# ZED-F9T.net
KiCad netlist of a schematic drawn in Altium Designer
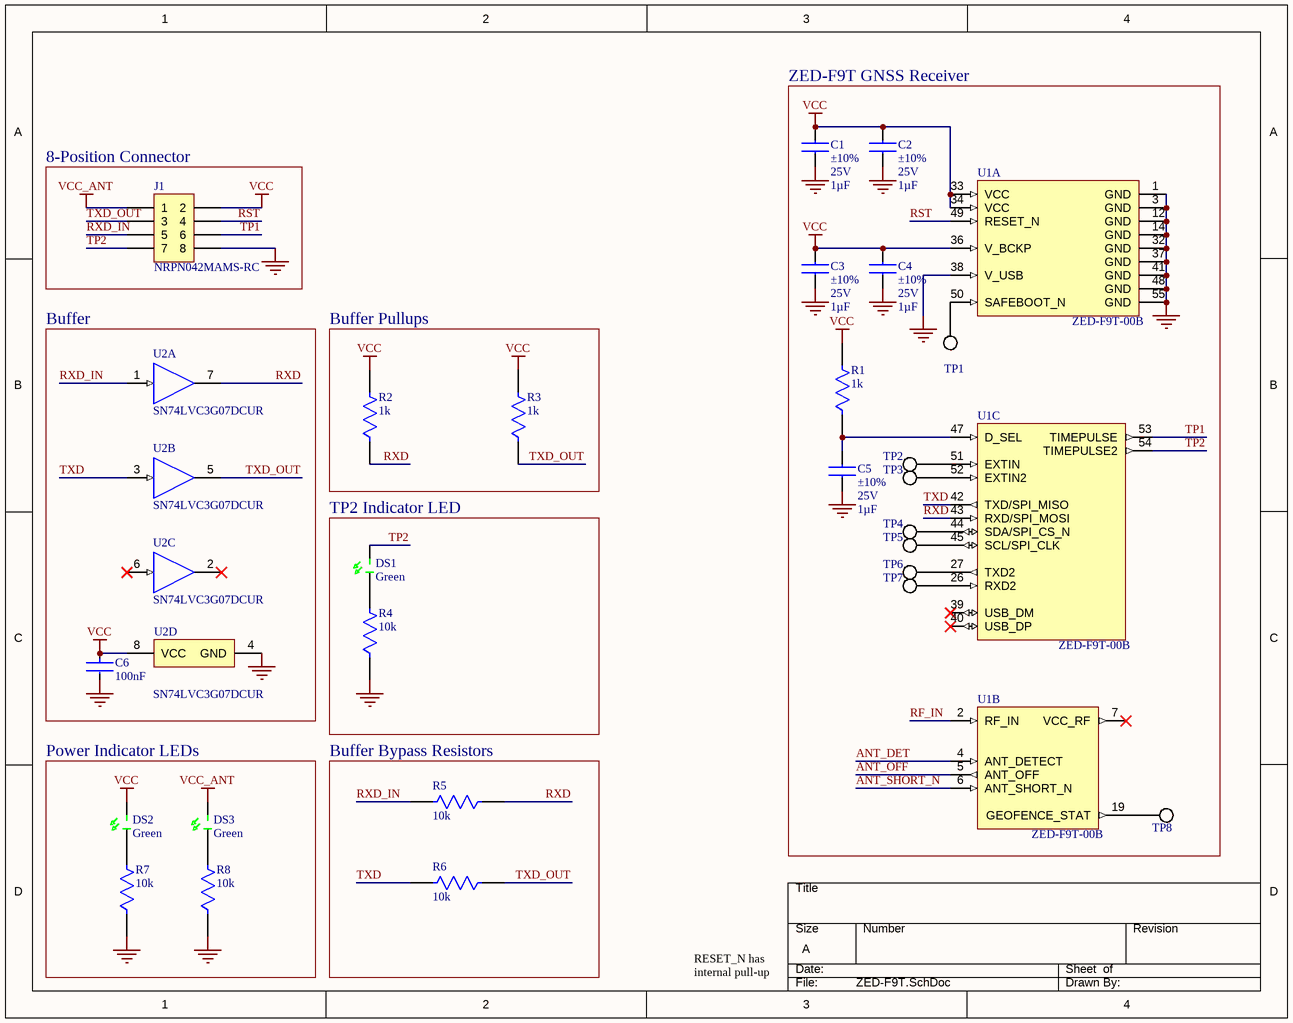
[diagram p0: ZED-F9T.SchDoc]

(export (version "E")
  (design (tool "Eeschema 10.0.6"))
  (components
    (comp (ref "C1")
      (value "Murata_GRM155R61E105KA12D")
      (footprint "CAPC1005X055N")
      (description "CAP, CER, X5R, 1UF, 10%, 25V, 0402, 0.55MM T")
      (fields
        (field (name "MANUFACTURER PART NUMBER") "GRM155R61E105KA12D")
        (field (name "TOLERANCE") "±10%")
        (field (name "VOLTAGE RATING") "25V")
        (field (name "MANUFACTURER") "Murata")
        (field (name "CAPACITANCE") "1µF")
      )
      (libsource (lib "RL Research Altium Server") (part "Capacitor_300mil"))
    )
    (comp (ref "C2")
      (value "Murata_GRM155R61E105KA12D")
      (footprint "CAPC1005X055N")
      (description "CAP, CER, X5R, 1UF, 10%, 25V, 0402, 0.55MM T")
      (fields
        (field (name "MANUFACTURER PART NUMBER") "GRM155R61E105KA12D")
        (field (name "TOLERANCE") "±10%")
        (field (name "VOLTAGE RATING") "25V")
        (field (name "MANUFACTURER") "Murata")
        (field (name "CAPACITANCE") "1µF")
      )
      (libsource (lib "RL Research Altium Server") (part "Capacitor_300mil"))
    )
    (comp (ref "C3")
      (value "Murata_GRM155R61E105KA12D")
      (footprint "CAPC1005X055N")
      (description "CAP, CER, X5R, 1UF, 10%, 25V, 0402, 0.55MM T")
      (fields
        (field (name "MANUFACTURER PART NUMBER") "GRM155R61E105KA12D")
        (field (name "TOLERANCE") "±10%")
        (field (name "VOLTAGE RATING") "25V")
        (field (name "MANUFACTURER") "Murata")
        (field (name "CAPACITANCE") "1µF")
      )
      (libsource (lib "RL Research Altium Server") (part "Capacitor_300mil"))
    )
    (comp (ref "C4")
      (value "Murata_GRM155R61E105KA12D")
      (footprint "CAPC1005X055N")
      (description "CAP, CER, X5R, 1UF, 10%, 25V, 0402, 0.55MM T")
      (fields
        (field (name "MANUFACTURER PART NUMBER") "GRM155R61E105KA12D")
        (field (name "TOLERANCE") "±10%")
        (field (name "VOLTAGE RATING") "25V")
        (field (name "MANUFACTURER") "Murata")
        (field (name "CAPACITANCE") "1µF")
      )
      (libsource (lib "RL Research Altium Server") (part "Capacitor_300mil"))
    )
    (comp (ref "C5")
      (value "Murata_GRM155R61E105KA12D")
      (footprint "CAPC1005X055N")
      (description "CAP, CER, X5R, 1UF, 10%, 25V, 0402, 0.55MM T")
      (fields
        (field (name "MANUFACTURER PART NUMBER") "GRM155R61E105KA12D")
        (field (name "TOLERANCE") "±10%")
        (field (name "VOLTAGE RATING") "25V")
        (field (name "MANUFACTURER") "Murata")
        (field (name "CAPACITANCE") "1µF")
      )
      (libsource (lib "RL Research Altium Server") (part "Capacitor_300mil"))
    )
    (comp (ref "C6")
      (value "100nF")
      (footprint "FP-0402-L_1_0_0_05-W_0_5-IPC_B")
      (description "None")
      (fields (field (name "TOLERANCE") "10%"))
      (libsource (lib "Altium Content Vault") (part "b4654b650e69147ec39a6b967a45e02"))
    )
    (comp (ref "DS1")
      (value "Lumex_SML-LXFM0603SUGCTR")
      (footprint "LEDS160X80X110-2N_LXFM0603-GR")
      (description "LED, GREEN, 574NM, 20MA, 20MCD MIN, 2.5VF MAX, 0603, 1.10MM T")
      (fields
        (field (name "INTERNAL PART NUMBER") "838-00422-00")
        (field (name "MANUFACTURER") "Lumex Opto/Components Inc.")
        (field (name "COLOR") "Green")
      )
      (libsource (lib "RL Research Altium Server") (part "LED_Green_300mil"))
    )
    (comp (ref "DS2")
      (value "Lumex_SML-LXFM0603SUGCTR")
      (footprint "LEDS160X80X110-2N_LXFM0603-GR")
      (description "LED, GREEN, 574NM, 20MA, 20MCD MIN, 2.5VF MAX, 0603, 1.10MM T")
      (fields
        (field (name "INTERNAL PART NUMBER") "838-00422-00")
        (field (name "MANUFACTURER") "Lumex Opto/Components Inc.")
        (field (name "COLOR") "Green")
      )
      (libsource (lib "RL Research Altium Server") (part "LED_Green_300mil"))
    )
    (comp (ref "DS3")
      (value "Lumex_SML-LXFM0603SUGCTR")
      (footprint "LEDS160X80X110-2N_LXFM0603-GR")
      (description "LED, GREEN, 574NM, 20MA, 20MCD MIN, 2.5VF MAX, 0603, 1.10MM T")
      (fields
        (field (name "INTERNAL PART NUMBER") "838-00422-00")
        (field (name "MANUFACTURER") "Lumex Opto/Components Inc.")
        (field (name "COLOR") "Green")
      )
      (libsource (lib "RL Research Altium Server") (part "LED_Green_300mil"))
    )
    (comp (ref "J1")
      (value "NRPN042MAMS-RC")
      (footprint "NRPN042MAMS-RC")
      (description "Dual Row 8 Position 2 mm Pitch Surface Mount Header")
      (fields (field (name "MANUFACTURER") "Sullins"))
      (libsource (lib "GNSS_Receiver_Library") (part "NRPN042MAMS-RC"))
    )
    (comp (ref "R1")
      (value "1k")
      (footprint "FP-RMCF0402-MFG")
      (description "1kΩ ±1% 0.063W 0402 Thick Film Chip Resistor AEC-Q200 compliant")
      (fields (field (name "TOLERANCE") "1%"))
      (libsource (lib "Altium Content Vault") (part "1029c3af85768c4190bb7ad29bc67b5"))
    )
    (comp (ref "R2")
      (value "1k")
      (footprint "FP-RMCF0402-MFG")
      (description "1kΩ ±1% 0.063W 0402 Thick Film Chip Resistor AEC-Q200 compliant")
      (fields (field (name "TOLERANCE") "1%"))
      (libsource (lib "Altium Content Vault") (part "1029c3af85768c4190bb7ad29bc67b5"))
    )
    (comp (ref "R3")
      (value "1k")
      (footprint "FP-RMCF0402-MFG")
      (description "1kΩ ±1% 0.063W 0402 Thick Film Chip Resistor AEC-Q200 compliant")
      (fields (field (name "TOLERANCE") "1%"))
      (libsource (lib "Altium Content Vault") (part "1029c3af85768c4190bb7ad29bc67b5"))
    )
    (comp (ref "R4")
      (value "10k")
      (footprint "FP-RMCF0402-IPC_C")
      (description "10kΩ ±1% 0.063W 0402 Thick Film Chip Resistor AEC-Q200 compliant")
      (fields (field (name "TOLERANCE") "1%"))
      (libsource (lib "Altium Content Vault") (part "1029c3af85768c4190bb7ad29bc67b5"))
    )
    (comp (ref "R5")
      (value "10k")
      (footprint "FP-RMCF0402-IPC_C")
      (description "10kΩ ±1% 0.063W 0402 Thick Film Chip Resistor AEC-Q200 compliant")
      (fields (field (name "TOLERANCE") "1%"))
      (libsource (lib "Altium Content Vault") (part "1029c3af85768c4190bb7ad29bc67b5"))
    )
    (comp (ref "R6")
      (value "10k")
      (footprint "FP-RMCF0402-IPC_C")
      (description "10kΩ ±1% 0.063W 0402 Thick Film Chip Resistor AEC-Q200 compliant")
      (fields (field (name "TOLERANCE") "1%"))
      (libsource (lib "Altium Content Vault") (part "1029c3af85768c4190bb7ad29bc67b5"))
    )
    (comp (ref "R7")
      (value "10k")
      (footprint "FP-RMCF0402-IPC_C")
      (description "10kΩ ±1% 0.063W 0402 Thick Film Chip Resistor AEC-Q200 compliant")
      (fields (field (name "TOLERANCE") "1%"))
      (libsource (lib "Altium Content Vault") (part "1029c3af85768c4190bb7ad29bc67b5"))
    )
    (comp (ref "R8")
      (value "10k")
      (footprint "FP-RMCF0402-IPC_C")
      (description "10kΩ ±1% 0.063W 0402 Thick Film Chip Resistor AEC-Q200 compliant")
      (fields (field (name "TOLERANCE") "1%"))
      (libsource (lib "Altium Content Vault") (part "1029c3af85768c4190bb7ad29bc67b5"))
    )
    (comp (ref "TP1")
      (value "SMT_100DIA")
      (footprint "TP001V_SMT_100DIA")
      (description "TEST POINT, PC, SMT, 1.00MM DIA")
      (libsource (lib "RL Research Altium Server") (part "TP_NoColor_001pin_No_BOM"))
    )
    (comp (ref "TP2")
      (value "SMT_100DIA")
      (footprint "TP001V_SMT_100DIA")
      (description "TEST POINT, PC, SMT, 1.00MM DIA")
      (libsource (lib "RL Research Altium Server") (part "TP_NoColor_001pin_No_BOM"))
    )
    (comp (ref "TP3")
      (value "SMT_100DIA")
      (footprint "TP001V_SMT_100DIA")
      (description "TEST POINT, PC, SMT, 1.00MM DIA")
      (libsource (lib "RL Research Altium Server") (part "TP_NoColor_001pin_No_BOM"))
    )
    (comp (ref "TP4")
      (value "SMT_100DIA")
      (footprint "TP001V_SMT_100DIA")
      (description "TEST POINT, PC, SMT, 1.00MM DIA")
      (libsource (lib "RL Research Altium Server") (part "TP_NoColor_001pin_No_BOM"))
    )
    (comp (ref "TP5")
      (value "SMT_100DIA")
      (footprint "TP001V_SMT_100DIA")
      (description "TEST POINT, PC, SMT, 1.00MM DIA")
      (libsource (lib "RL Research Altium Server") (part "TP_NoColor_001pin_No_BOM"))
    )
    (comp (ref "TP6")
      (value "SMT_100DIA")
      (footprint "TP001V_SMT_100DIA")
      (description "TEST POINT, PC, SMT, 1.00MM DIA")
      (libsource (lib "RL Research Altium Server") (part "TP_NoColor_001pin_No_BOM"))
    )
    (comp (ref "TP7")
      (value "SMT_100DIA")
      (footprint "TP001V_SMT_100DIA")
      (description "TEST POINT, PC, SMT, 1.00MM DIA")
      (libsource (lib "RL Research Altium Server") (part "TP_NoColor_001pin_No_BOM"))
    )
    (comp (ref "TP8")
      (value "SMT_100DIA")
      (footprint "TP001V_SMT_100DIA")
      (description "TEST POINT, PC, SMT, 1.00MM DIA")
      (libsource (lib "RL Research Altium Server") (part "TP_NoColor_001pin_No_BOM"))
    )
    (comp (ref "U1")
      (value "ZED-F9T-00B")
      (footprint "GPS_ZED-F9T")
      (description "Multi-band GNSS Receiver with Nanosecond-level Timing Accuracy")
      (fields (field (name "MANUFACTURER") "u-blox"))
      (libsource (lib "GNSS_Receiver_Library") (part "GPS_ZED-F9T"))
    )
    (comp (ref "U2")
      (value "SN74LVC3G07DCUR")
      (footprint "DCU0008A_N")
      (description "Triple Buffer/Driver With Open-Drain Output, DCU0008A, LARGE T&R")
      (fields
        (field (name "GENERIC PART NUMBER") "SN74LVC3G07")
        (field (name "MANUFACTURER") "Texas Instruments")
      )
      (libsource (lib "Altium Content Vault") (part "TI-SN74XXX3G0X-XX-8"))
    )
  )
  (nets
    (net (code "1") (name "/ANT_DET") (class "Default")
      (node (ref "U1") (pin "4") (pinfunction "ANT_DETECT_4") (pintype "input"))
    )
    (net (code "2") (name "/ANT_OFF") (class "Default")
      (node (ref "U1") (pin "5") (pinfunction "ANT_OFF_5") (pintype "output"))
    )
    (net (code "3") (name "/ANT_SHORT_N") (class "Default")
      (node (ref "U1") (pin "6") (pinfunction "ANT_SHORT_N_6") (pintype "input"))
    )
    (net (code "4") (name "/RF_IN") (class "Default")
      (node (ref "U1") (pin "2") (pinfunction "RF_IN_2") (pintype "input"))
    )
    (net (code "5") (name "/RST") (class "Default")
      (node (ref "J1") (pin "4") (pinfunction "4_4") (pintype "passive"))
      (node (ref "U1") (pin "49") (pinfunction "RESET_N_49") (pintype "input"))
    )
    (net (code "6") (name "/RXD") (class "Default")
      (node (ref "R2") (pin "1") (pinfunction "1_1") (pintype "passive"))
      (node (ref "R5") (pin "1") (pinfunction "1_1") (pintype "passive"))
      (node (ref "U1") (pin "43") (pinfunction "RXD/SPI_MOSI_43") (pintype "input"))
      (node (ref "U2") (pin "7") (pinfunction "1Y_7") (pintype "open_collector"))
    )
    (net (code "7") (name "/RXD_IN") (class "Default")
      (node (ref "J1") (pin "5") (pinfunction "5_5") (pintype "passive"))
      (node (ref "R5") (pin "2") (pinfunction "2_2") (pintype "passive"))
      (node (ref "U2") (pin "1") (pinfunction "1A_1") (pintype "input"))
    )
    (net (code "8") (name "/TP1") (class "Default")
      (node (ref "J1") (pin "6") (pinfunction "6_6") (pintype "passive"))
      (node (ref "U1") (pin "53") (pinfunction "TIMEPULSE_53") (pintype "output"))
    )
    (net (code "9") (name "/TP2") (class "Default")
      (node (ref "DS1") (pin "A") (pinfunction "Anode_A") (pintype "passive"))
      (node (ref "J1") (pin "7") (pinfunction "7_7") (pintype "passive"))
      (node (ref "U1") (pin "54") (pinfunction "TIMEPULSE2_54") (pintype "output"))
    )
    (net (code "10") (name "/TXD") (class "Default")
      (node (ref "R6") (pin "2") (pinfunction "2_2") (pintype "passive"))
      (node (ref "U1") (pin "42") (pinfunction "TXD/SPI_MISO_42") (pintype "output"))
      (node (ref "U2") (pin "3") (pinfunction "2A_3") (pintype "input"))
    )
    (net (code "11") (name "/TXD_OUT") (class "Default")
      (node (ref "J1") (pin "3") (pinfunction "3_3") (pintype "passive"))
      (node (ref "R3") (pin "1") (pinfunction "1_1") (pintype "passive"))
      (node (ref "R6") (pin "1") (pinfunction "1_1") (pintype "passive"))
      (node (ref "U2") (pin "5") (pinfunction "2Y_5") (pintype "open_collector"))
    )
    (net (code "12") (name "GND") (class "Default")
      (node (ref "C1") (pin "2") (pinfunction "2_2") (pintype "passive"))
      (node (ref "C2") (pin "2") (pinfunction "2_2") (pintype "passive"))
      (node (ref "C3") (pin "2") (pinfunction "2_2") (pintype "passive"))
      (node (ref "C4") (pin "2") (pinfunction "2_2") (pintype "passive"))
      (node (ref "C5") (pin "2") (pinfunction "2_2") (pintype "passive"))
      (node (ref "C6") (pin "2") (pinfunction "2_2") (pintype "passive"))
      (node (ref "J1") (pin "8") (pinfunction "8_8") (pintype "passive"))
      (node (ref "R4") (pin "1") (pinfunction "1_1") (pintype "passive"))
      (node (ref "R7") (pin "1") (pinfunction "1_1") (pintype "passive"))
      (node (ref "R8") (pin "1") (pinfunction "1_1") (pintype "passive"))
      (node (ref "U1") (pin "1") (pinfunction "GND_1") (pintype "passive"))
      (node (ref "U1") (pin "12") (pinfunction "GND_12") (pintype "passive"))
      (node (ref "U1") (pin "14") (pinfunction "GND_14") (pintype "passive"))
      (node (ref "U1") (pin "3") (pinfunction "GND_3") (pintype "passive"))
      (node (ref "U1") (pin "32") (pinfunction "GND_32") (pintype "passive"))
      (node (ref "U1") (pin "37") (pinfunction "GND_37") (pintype "passive"))
      (node (ref "U1") (pin "38") (pinfunction "V_USB_38") (pintype "input"))
      (node (ref "U1") (pin "41") (pinfunction "GND_41") (pintype "passive"))
      (node (ref "U1") (pin "48") (pinfunction "GND_48") (pintype "passive"))
      (node (ref "U1") (pin "55") (pinfunction "GND_55") (pintype "passive"))
      (node (ref "U2") (pin "4") (pinfunction "GND_4") (pintype "power_in"))
    )
    (net (code "13") (name "Net-(DS1-Cathode)") (class "Default")
      (node (ref "DS1") (pin "K") (pinfunction "Cathode_K") (pintype "passive"))
      (node (ref "R4") (pin "2") (pinfunction "2_2") (pintype "passive"))
    )
    (net (code "14") (name "Net-(DS2-Cathode)") (class "Default")
      (node (ref "DS2") (pin "K") (pinfunction "Cathode_K") (pintype "passive"))
      (node (ref "R7") (pin "2") (pinfunction "2_2") (pintype "passive"))
    )
    (net (code "15") (name "Net-(DS3-Cathode)") (class "Default")
      (node (ref "DS3") (pin "K") (pinfunction "Cathode_K") (pintype "passive"))
      (node (ref "R8") (pin "2") (pinfunction "2_2") (pintype "passive"))
    )
    (net (code "16") (name "Net-(U1A-SAFEBOOT_N)") (class "Default")
      (node (ref "TP1") (pin "1") (pinfunction "1_1") (pintype "passive"))
      (node (ref "U1") (pin "50") (pinfunction "SAFEBOOT_N_50") (pintype "input"))
    )
    (net (code "17") (name "Net-(U1B-GEOFENCE_STAT)") (class "Default")
      (node (ref "TP8") (pin "1") (pinfunction "1_1") (pintype "passive"))
      (node (ref "U1") (pin "19") (pinfunction "GEOFENCE_STAT_19") (pintype "output"))
    )
    (net (code "18") (name "Net-(U1C-D_SEL)") (class "Default")
      (node (ref "C5") (pin "1") (pinfunction "1_1") (pintype "passive"))
      (node (ref "R1") (pin "1") (pinfunction "1_1") (pintype "passive"))
      (node (ref "U1") (pin "47") (pinfunction "D_SEL_47") (pintype "input"))
    )
    (net (code "19") (name "Net-(U1C-EXTIN)") (class "Default")
      (node (ref "TP2") (pin "1") (pinfunction "1_1") (pintype "passive"))
      (node (ref "U1") (pin "51") (pinfunction "EXTIN_51") (pintype "input"))
    )
    (net (code "20") (name "Net-(U1C-EXTIN2)") (class "Default")
      (node (ref "TP3") (pin "1") (pinfunction "1_1") (pintype "passive"))
      (node (ref "U1") (pin "52") (pinfunction "EXTIN2_52") (pintype "input"))
    )
    (net (code "21") (name "Net-(U1C-RXD2)") (class "Default")
      (node (ref "TP7") (pin "1") (pinfunction "1_1") (pintype "passive"))
      (node (ref "U1") (pin "26") (pinfunction "RXD2_26") (pintype "input"))
    )
    (net (code "22") (name "Net-(U1C-SCL{slash}SPI_CLK)") (class "Default")
      (node (ref "TP5") (pin "1") (pinfunction "1_1") (pintype "passive"))
      (node (ref "U1") (pin "45") (pinfunction "SCL/SPI_CLK_45") (pintype "bidirectional"))
    )
    (net (code "23") (name "Net-(U1C-SDA{slash}SPI_CS_N)") (class "Default")
      (node (ref "TP4") (pin "1") (pinfunction "1_1") (pintype "passive"))
      (node (ref "U1") (pin "44") (pinfunction "SDA/SPI_CS_N_44") (pintype "bidirectional"))
    )
    (net (code "24") (name "Net-(U1C-TXD2)") (class "Default")
      (node (ref "TP6") (pin "1") (pinfunction "1_1") (pintype "passive"))
      (node (ref "U1") (pin "27") (pinfunction "TXD2_27") (pintype "output"))
    )
    (net (code "25") (name "VCC") (class "Default")
      (node (ref "C1") (pin "1") (pinfunction "1_1") (pintype "passive"))
      (node (ref "C2") (pin "1") (pinfunction "1_1") (pintype "passive"))
      (node (ref "C3") (pin "1") (pinfunction "1_1") (pintype "passive"))
      (node (ref "C4") (pin "1") (pinfunction "1_1") (pintype "passive"))
      (node (ref "C6") (pin "1") (pinfunction "1_1") (pintype "passive"))
      (node (ref "DS2") (pin "A") (pinfunction "Anode_A") (pintype "passive"))
      (node (ref "J1") (pin "2") (pinfunction "2_2") (pintype "passive"))
      (node (ref "R1") (pin "2") (pinfunction "2_2") (pintype "passive"))
      (node (ref "R2") (pin "2") (pinfunction "2_2") (pintype "passive"))
      (node (ref "R3") (pin "2") (pinfunction "2_2") (pintype "passive"))
      (node (ref "U1") (pin "33") (pinfunction "VCC_33") (pintype "input"))
      (node (ref "U1") (pin "34") (pinfunction "VCC_34") (pintype "input"))
      (node (ref "U1") (pin "36") (pinfunction "V_BCKP_36") (pintype "input"))
      (node (ref "U2") (pin "8") (pinfunction "VCC_8") (pintype "power_in"))
    )
    (net (code "26") (name "VCC_ANT") (class "Default")
      (node (ref "DS3") (pin "A") (pinfunction "Anode_A") (pintype "passive"))
      (node (ref "J1") (pin "1") (pinfunction "1_1") (pintype "passive"))
    )
    (net (code "27") (name "unconnected-(U1B-VCC_RF-Pad7)") (class "Default")
      (node (ref "U1") (pin "7") (pinfunction "VCC_RF_7") (pintype "output+no_connect"))
    )
    (net (code "28") (name "unconnected-(U1C-USB_DM-Pad39)") (class "Default")
      (node (ref "U1") (pin "39") (pinfunction "USB_DM_39") (pintype "bidirectional+no_connect"))
    )
    (net (code "29") (name "unconnected-(U1C-USB_DP-Pad40)") (class "Default")
      (node (ref "U1") (pin "40") (pinfunction "USB_DP_40") (pintype "bidirectional+no_connect"))
    )
    (net (code "30") (name "unconnected-(U2C-3A-Pad6)") (class "Default")
      (node (ref "U2") (pin "6") (pinfunction "3A_6") (pintype "input+no_connect"))
    )
    (net (code "31") (name "unconnected-(U2C-3Y-Pad2)") (class "Default")
      (node (ref "U2") (pin "2") (pinfunction "3Y_2") (pintype "open_collector+no_connect"))
    )
  )
)
